# JP_Eagle_Daughter_Board.net
KiCad netlist of a schematic drawn in EAGLE
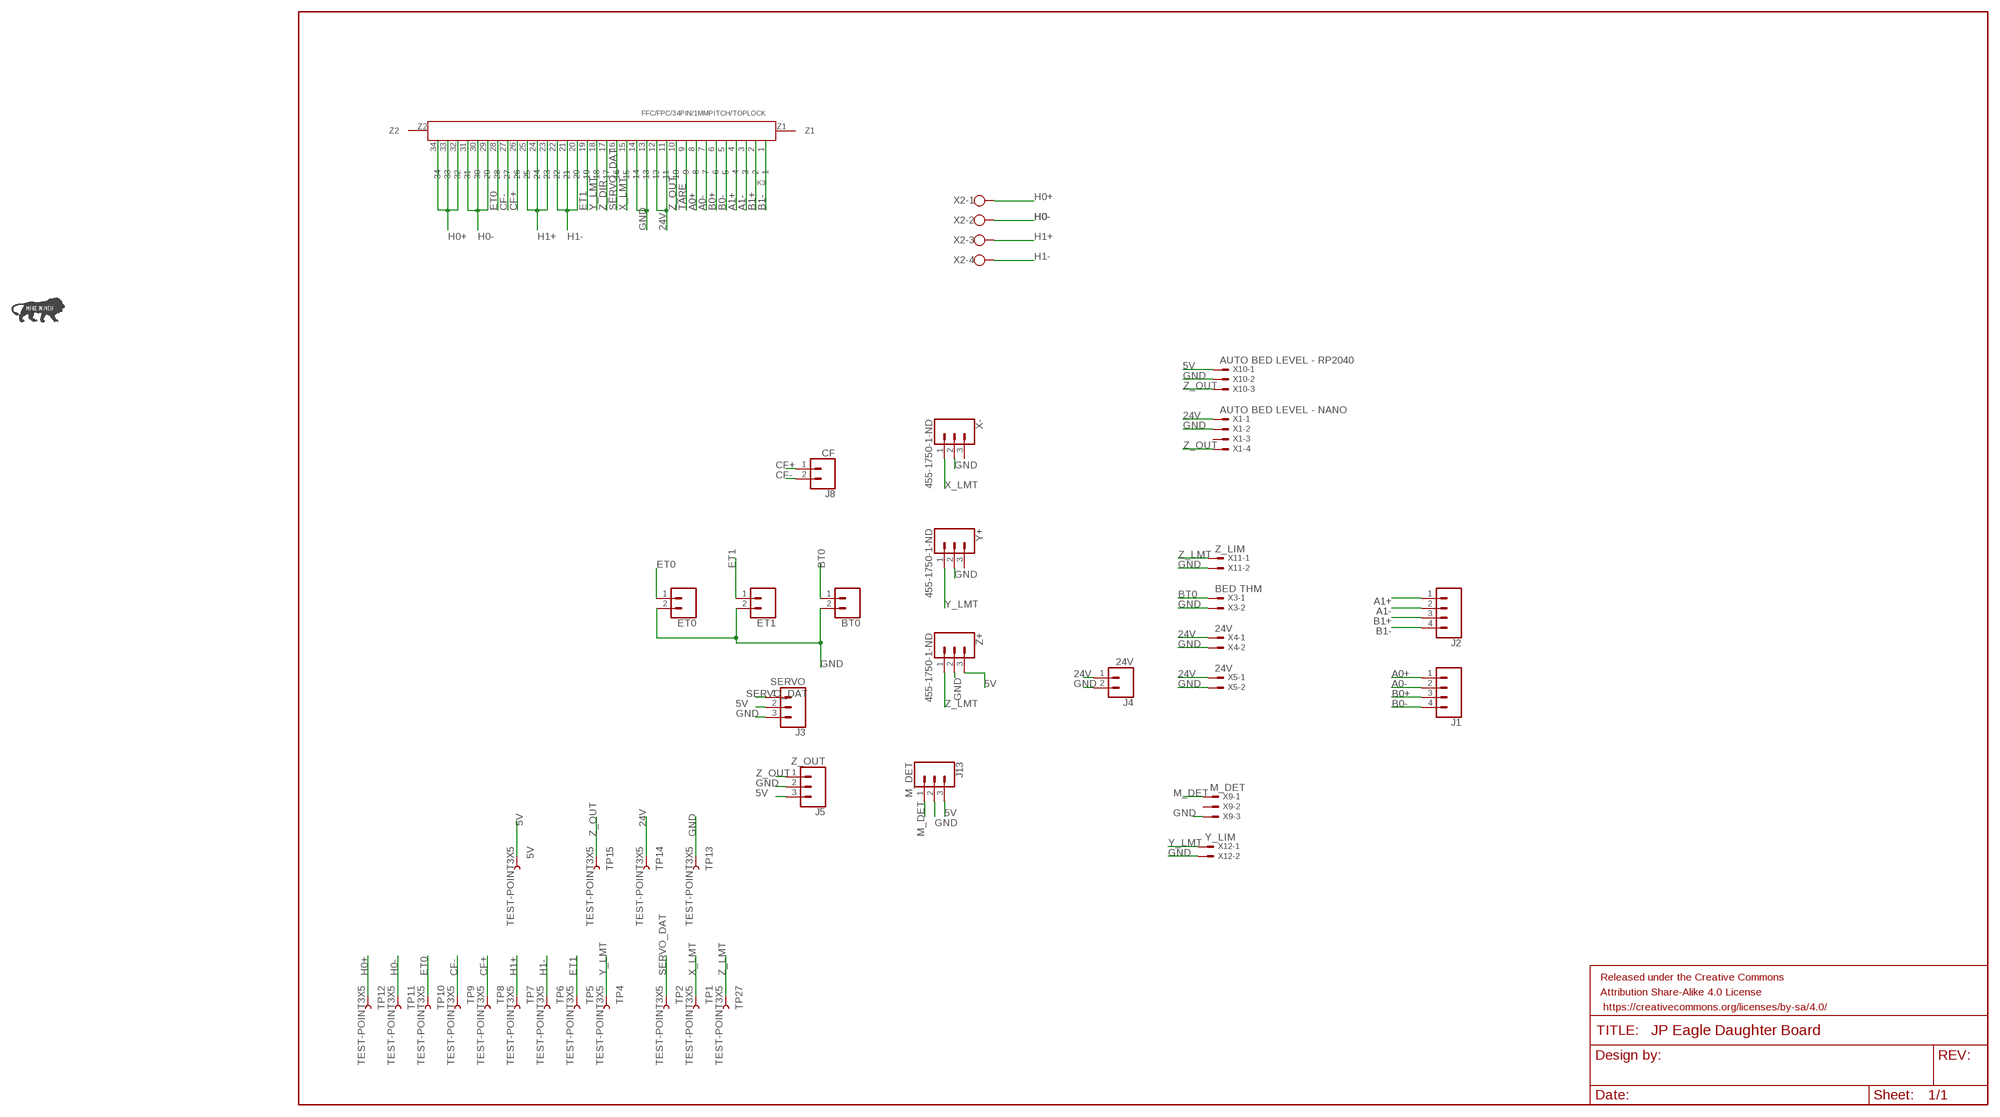
[diagram p0: schematic, sheet 1]

(export (version "E")
  (design (tool "Eeschema 10.0.6"))
  (components
    (comp (ref "5V")
      (value "TEST-POINT3X5")
      (footprint "eagle-import:PAD.03X.05")
      (libsource (lib "eagle-import") (part "TEST-POINT3X5"))
    )
    (comp (ref "BT0")
      (value "CONN_02")
      (footprint "eagle-import:1X02")
      (libsource (lib "eagle-import") (part "CONN_02"))
    )
    (comp (ref "ET0")
      (value "CONN_02")
      (footprint "eagle-import:1X02")
      (libsource (lib "eagle-import") (part "CONN_02"))
    )
    (comp (ref "ET1")
      (value "CONN_02")
      (footprint "eagle-import:1X02")
      (libsource (lib "eagle-import") (part "CONN_02"))
    )
    (comp (ref "FRAME1")
      (value "FRAME-LEDGER")
      (footprint "eagle-import:CREATIVE_COMMONS")
      (libsource (lib "eagle-import") (part "FRAME-LEDGER"))
    )
    (comp (ref "J1")
      (value "CONN_04")
      (footprint "eagle-import:1X04")
      (libsource (lib "eagle-import") (part "CONN_04"))
    )
    (comp (ref "J2")
      (value "CONN_04")
      (footprint "eagle-import:1X04")
      (libsource (lib "eagle-import") (part "CONN_04"))
    )
    (comp (ref "J3")
      (value "SERVO")
      (footprint "eagle-import:1X03")
      (libsource (lib "eagle-import") (part "CONN_03"))
    )
    (comp (ref "J4")
      (value "24V")
      (footprint "eagle-import:1X02")
      (libsource (lib "eagle-import") (part "CONN_02"))
    )
    (comp (ref "J5")
      (value "Z_OUT")
      (footprint "eagle-import:1X03")
      (libsource (lib "eagle-import") (part "CONN_03"))
    )
    (comp (ref "J8")
      (value "CF")
      (footprint "eagle-import:1X02")
      (libsource (lib "eagle-import") (part "CONN_02"))
    )
    (comp (ref "J13")
      (value "M_DET")
      (footprint "eagle-import:1X03")
      (libsource (lib "eagle-import") (part "CONN_03"))
    )
    (comp (ref "K3")
      (value "FFC/FPC/34PIN/1MMPITCH/TOPLOCK")
      (footprint "eagle-import:34PIN_1MMPITCH_FFC_FPC")
      (libsource (lib "eagle-import") (part "FFC/FPC/34PIN/1MMPITCH/TOPLOCK"))
    )
    (comp (ref "TP1")
      (value "TEST-POINT3X5")
      (footprint "eagle-import:PAD.03X.05")
      (libsource (lib "eagle-import") (part "TEST-POINT3X5"))
    )
    (comp (ref "TP2")
      (value "TEST-POINT3X5")
      (footprint "eagle-import:PAD.03X.05")
      (libsource (lib "eagle-import") (part "TEST-POINT3X5"))
    )
    (comp (ref "TP4")
      (value "TEST-POINT3X5")
      (footprint "eagle-import:PAD.03X.05")
      (libsource (lib "eagle-import") (part "TEST-POINT3X5"))
    )
    (comp (ref "TP5")
      (value "TEST-POINT3X5")
      (footprint "eagle-import:PAD.03X.05")
      (libsource (lib "eagle-import") (part "TEST-POINT3X5"))
    )
    (comp (ref "TP6")
      (value "TEST-POINT3X5")
      (footprint "eagle-import:PAD.03X.05")
      (libsource (lib "eagle-import") (part "TEST-POINT3X5"))
    )
    (comp (ref "TP7")
      (value "TEST-POINT3X5")
      (footprint "eagle-import:PAD.03X.05")
      (libsource (lib "eagle-import") (part "TEST-POINT3X5"))
    )
    (comp (ref "TP8")
      (value "TEST-POINT3X5")
      (footprint "eagle-import:PAD.03X.05")
      (libsource (lib "eagle-import") (part "TEST-POINT3X5"))
    )
    (comp (ref "TP9")
      (value "TEST-POINT3X5")
      (footprint "eagle-import:PAD.03X.05")
      (libsource (lib "eagle-import") (part "TEST-POINT3X5"))
    )
    (comp (ref "TP10")
      (value "TEST-POINT3X5")
      (footprint "eagle-import:PAD.03X.05")
      (libsource (lib "eagle-import") (part "TEST-POINT3X5"))
    )
    (comp (ref "TP11")
      (value "TEST-POINT3X5")
      (footprint "eagle-import:PAD.03X.05")
      (libsource (lib "eagle-import") (part "TEST-POINT3X5"))
    )
    (comp (ref "TP12")
      (value "TEST-POINT3X5")
      (footprint "eagle-import:PAD.03X.05")
      (libsource (lib "eagle-import") (part "TEST-POINT3X5"))
    )
    (comp (ref "TP13")
      (value "TEST-POINT3X5")
      (footprint "eagle-import:PAD.03X.05")
      (libsource (lib "eagle-import") (part "TEST-POINT3X5"))
    )
    (comp (ref "TP14")
      (value "TEST-POINT3X5")
      (footprint "eagle-import:PAD.03X.05")
      (libsource (lib "eagle-import") (part "TEST-POINT3X5"))
    )
    (comp (ref "TP15")
      (value "TEST-POINT3X5")
      (footprint "eagle-import:PAD.03X.05")
      (libsource (lib "eagle-import") (part "TEST-POINT3X5"))
    )
    (comp (ref "TP27")
      (value "TEST-POINT3X5")
      (footprint "eagle-import:PAD.03X.05")
      (libsource (lib "eagle-import") (part "TEST-POINT3X5"))
    )
    (comp (ref "U$2")
      (value "MAKEININDIA")
      (footprint "eagle-import:MAKEININDIA")
      (libsource (lib "eagle-import") (part "MAKEININDIA"))
    )
    (comp (ref "X-")
      (value "455-1750-1-ND")
      (footprint "eagle-import:1X03")
      (libsource (lib "eagle-import") (part "CONN_03"))
    )
    (comp (ref "X1")
      (value "AUTO BED LEVEL - NANO")
      (footprint "eagle-import:JST-XH-04-PACKAGE-LONG-PAD")
      (libsource (lib "eagle-import") (part "JST-XH-04-PIN-LONG-PAD"))
    )
    (comp (ref "X2")
      (value "W237-4")
      (footprint "eagle-import:W237-4")
      (libsource (lib "eagle-import") (part "W237-4"))
    )
    (comp (ref "X3")
      (value "BED THM")
      (footprint "eagle-import:JST-XH-02-PACKAGE-LONG-PAD")
      (libsource (lib "eagle-import") (part "JST-XH-02-PIN-LONG-PAD"))
    )
    (comp (ref "X4")
      (value "24V")
      (footprint "eagle-import:JST-XH-02-PACKAGE-LONG-PAD")
      (libsource (lib "eagle-import") (part "JST-XH-02-PIN-LONG-PAD"))
    )
    (comp (ref "X5")
      (value "24V")
      (footprint "eagle-import:JST-XH-02-PACKAGE-LONG-PAD")
      (libsource (lib "eagle-import") (part "JST-XH-02-PIN-LONG-PAD"))
    )
    (comp (ref "X9")
      (value "M_DET")
      (footprint "eagle-import:JST-XH-03-PACKAGE-LONG-PAD")
      (libsource (lib "eagle-import") (part "JST-XH-03-PIN-LONG-PAD"))
    )
    (comp (ref "X10")
      (value "AUTO BED LEVEL - RP2040")
      (footprint "eagle-import:JST-XH-03-PACKAGE-LONG-PAD")
      (libsource (lib "eagle-import") (part "JST-XH-03-PIN-LONG-PAD"))
    )
    (comp (ref "X11")
      (value "Z_LIM")
      (footprint "eagle-import:JST-XH-02-PACKAGE-LONG-PAD")
      (libsource (lib "eagle-import") (part "JST-XH-02-PIN-LONG-PAD"))
    )
    (comp (ref "X12")
      (value "Y_LIM")
      (footprint "eagle-import:JST-XH-02-PACKAGE-LONG-PAD")
      (libsource (lib "eagle-import") (part "JST-XH-02-PIN-LONG-PAD"))
    )
    (comp (ref "Y+")
      (value "455-1750-1-ND")
      (footprint "eagle-import:1X03")
      (libsource (lib "eagle-import") (part "CONN_03"))
    )
    (comp (ref "Z+")
      (value "455-1750-1-ND")
      (footprint "eagle-import:1X03")
      (libsource (lib "eagle-import") (part "CONN_03"))
    )
  )
  (nets
    (net (code "1") (name "/5V") (class "Default")
      (node (ref "5V") (pin "P$1") (pinfunction "1_P$1") (pintype "bidirectional"))
      (node (ref "J13") (pin "3") (pinfunction "3_3") (pintype "passive"))
      (node (ref "J3") (pin "2") (pinfunction "2_2") (pintype "passive"))
      (node (ref "J5") (pin "3") (pinfunction "3_3") (pintype "passive"))
      (node (ref "X10") (pin "1") (pinfunction "S_1") (pintype "passive"))
      (node (ref "Z+") (pin "3") (pinfunction "3_3") (pintype "passive"))
    )
    (net (code "2") (name "/24V") (class "Default")
      (node (ref "J4") (pin "1") (pinfunction "1_1") (pintype "passive"))
      (node (ref "K3") (pin "11") (pinfunction "11_11") (pintype "bidirectional"))
      (node (ref "K3") (pin "12") (pinfunction "12_12") (pintype "bidirectional"))
      (node (ref "TP14") (pin "P$1") (pinfunction "1_P$1") (pintype "bidirectional"))
      (node (ref "X1") (pin "1") (pinfunction "S_1") (pintype "passive"))
      (node (ref "X4") (pin "1") (pinfunction "S_1") (pintype "passive"))
      (node (ref "X5") (pin "1") (pinfunction "S_1") (pintype "passive"))
    )
    (net (code "3") (name "/A0+") (class "Default")
      (node (ref "J1") (pin "1") (pinfunction "1_1") (pintype "passive"))
      (node (ref "K3") (pin "8") (pinfunction "8_8") (pintype "bidirectional"))
    )
    (net (code "4") (name "/A0-") (class "Default")
      (node (ref "J1") (pin "2") (pinfunction "2_2") (pintype "passive"))
      (node (ref "K3") (pin "7") (pinfunction "7_7") (pintype "bidirectional"))
    )
    (net (code "5") (name "/A1+") (class "Default")
      (node (ref "J2") (pin "1") (pinfunction "1_1") (pintype "passive"))
      (node (ref "K3") (pin "4") (pinfunction "4_4") (pintype "bidirectional"))
    )
    (net (code "6") (name "/A1-") (class "Default")
      (node (ref "J2") (pin "2") (pinfunction "2_2") (pintype "passive"))
      (node (ref "K3") (pin "3") (pinfunction "3_3") (pintype "bidirectional"))
    )
    (net (code "7") (name "/B0+") (class "Default")
      (node (ref "J1") (pin "3") (pinfunction "3_3") (pintype "passive"))
      (node (ref "K3") (pin "6") (pinfunction "6_6") (pintype "bidirectional"))
    )
    (net (code "8") (name "/B0-") (class "Default")
      (node (ref "J1") (pin "4") (pinfunction "4_4") (pintype "passive"))
      (node (ref "K3") (pin "5") (pinfunction "5_5") (pintype "bidirectional"))
    )
    (net (code "9") (name "/B1+") (class "Default")
      (node (ref "J2") (pin "3") (pinfunction "3_3") (pintype "passive"))
      (node (ref "K3") (pin "2") (pinfunction "2_2") (pintype "bidirectional"))
    )
    (net (code "10") (name "/B1-") (class "Default")
      (node (ref "J2") (pin "4") (pinfunction "4_4") (pintype "passive"))
      (node (ref "K3") (pin "1") (pinfunction "1_1") (pintype "bidirectional"))
    )
    (net (code "11") (name "/BT0") (class "Default")
      (node (ref "BT0") (pin "1") (pinfunction "1_1") (pintype "passive"))
      (node (ref "X3") (pin "1") (pinfunction "S_1") (pintype "passive"))
    )
    (net (code "12") (name "/CF+") (class "Default")
      (node (ref "J8") (pin "1") (pinfunction "1_1") (pintype "passive"))
      (node (ref "K3") (pin "26") (pinfunction "26_26") (pintype "bidirectional"))
      (node (ref "TP8") (pin "P$1") (pinfunction "1_P$1") (pintype "bidirectional"))
    )
    (net (code "13") (name "/CF-") (class "Default")
      (node (ref "J8") (pin "2") (pinfunction "2_2") (pintype "passive"))
      (node (ref "K3") (pin "27") (pinfunction "27_27") (pintype "bidirectional"))
      (node (ref "TP9") (pin "P$1") (pinfunction "1_P$1") (pintype "bidirectional"))
    )
    (net (code "14") (name "/ET0") (class "Default")
      (node (ref "ET0") (pin "1") (pinfunction "1_1") (pintype "passive"))
      (node (ref "K3") (pin "28") (pinfunction "28_28") (pintype "bidirectional"))
      (node (ref "TP10") (pin "P$1") (pinfunction "1_P$1") (pintype "bidirectional"))
    )
    (net (code "15") (name "/ET1") (class "Default")
      (node (ref "ET1") (pin "1") (pinfunction "1_1") (pintype "passive"))
      (node (ref "K3") (pin "19") (pinfunction "19_19") (pintype "bidirectional"))
      (node (ref "TP5") (pin "P$1") (pinfunction "1_P$1") (pintype "bidirectional"))
    )
    (net (code "16") (name "/GND") (class "Default")
      (node (ref "BT0") (pin "2") (pinfunction "2_2") (pintype "passive"))
      (node (ref "ET0") (pin "2") (pinfunction "2_2") (pintype "passive"))
      (node (ref "ET1") (pin "2") (pinfunction "2_2") (pintype "passive"))
      (node (ref "J13") (pin "2") (pinfunction "2_2") (pintype "passive"))
      (node (ref "J3") (pin "3") (pinfunction "3_3") (pintype "passive"))
      (node (ref "J4") (pin "2") (pinfunction "2_2") (pintype "passive"))
      (node (ref "J5") (pin "2") (pinfunction "2_2") (pintype "passive"))
      (node (ref "K3") (pin "13") (pinfunction "13_13") (pintype "bidirectional"))
      (node (ref "K3") (pin "14") (pinfunction "14_14") (pintype "bidirectional"))
      (node (ref "TP13") (pin "P$1") (pinfunction "1_P$1") (pintype "bidirectional"))
      (node (ref "X-") (pin "2") (pinfunction "2_2") (pintype "passive"))
      (node (ref "X1") (pin "2") (pinfunction "S_2") (pintype "passive"))
      (node (ref "X10") (pin "2") (pinfunction "S_2") (pintype "passive"))
      (node (ref "X11") (pin "2") (pinfunction "S_2") (pintype "passive"))
      (node (ref "X12") (pin "2") (pinfunction "S_2") (pintype "passive"))
      (node (ref "X3") (pin "2") (pinfunction "S_2") (pintype "passive"))
      (node (ref "X4") (pin "2") (pinfunction "S_2") (pintype "passive"))
      (node (ref "X5") (pin "2") (pinfunction "S_2") (pintype "passive"))
      (node (ref "X9") (pin "3") (pinfunction "S_3") (pintype "passive"))
      (node (ref "Y+") (pin "2") (pinfunction "2_2") (pintype "passive"))
      (node (ref "Z+") (pin "2") (pinfunction "2_2") (pintype "passive"))
    )
    (net (code "17") (name "/H0+") (class "Default")
      (node (ref "K3") (pin "32") (pinfunction "32_32") (pintype "bidirectional"))
      (node (ref "K3") (pin "33") (pinfunction "33_33") (pintype "bidirectional"))
      (node (ref "K3") (pin "34") (pinfunction "34_34") (pintype "bidirectional"))
      (node (ref "TP12") (pin "P$1") (pinfunction "1_P$1") (pintype "bidirectional"))
      (node (ref "X2") (pin "1") (pinfunction "KL_1") (pintype "passive"))
    )
    (net (code "18") (name "/H0-") (class "Default")
      (node (ref "K3") (pin "29") (pinfunction "29_29") (pintype "bidirectional"))
      (node (ref "K3") (pin "30") (pinfunction "30_30") (pintype "bidirectional"))
      (node (ref "K3") (pin "31") (pinfunction "31_31") (pintype "bidirectional"))
      (node (ref "TP11") (pin "P$1") (pinfunction "1_P$1") (pintype "bidirectional"))
      (node (ref "X2") (pin "2") (pinfunction "KL_2") (pintype "passive"))
    )
    (net (code "19") (name "/H1+") (class "Default")
      (node (ref "K3") (pin "23") (pinfunction "23_23") (pintype "bidirectional"))
      (node (ref "K3") (pin "24") (pinfunction "24_24") (pintype "bidirectional"))
      (node (ref "K3") (pin "25") (pinfunction "25_25") (pintype "bidirectional"))
      (node (ref "TP7") (pin "P$1") (pinfunction "1_P$1") (pintype "bidirectional"))
      (node (ref "X2") (pin "3") (pinfunction "KL_3") (pintype "passive"))
    )
    (net (code "20") (name "/H1-") (class "Default")
      (node (ref "K3") (pin "20") (pinfunction "20_20") (pintype "bidirectional"))
      (node (ref "K3") (pin "21") (pinfunction "21_21") (pintype "bidirectional"))
      (node (ref "K3") (pin "22") (pinfunction "22_22") (pintype "bidirectional"))
      (node (ref "TP6") (pin "P$1") (pinfunction "1_P$1") (pintype "bidirectional"))
      (node (ref "X2") (pin "4") (pinfunction "KL_4") (pintype "passive"))
    )
    (net (code "21") (name "/M_DET") (class "Default")
      (node (ref "J13") (pin "1") (pinfunction "1_1") (pintype "passive"))
      (node (ref "X9") (pin "1") (pinfunction "S_1") (pintype "passive"))
    )
    (net (code "22") (name "/SERVO_DAT") (class "Default")
      (node (ref "J3") (pin "1") (pinfunction "1_1") (pintype "passive"))
      (node (ref "K3") (pin "16") (pinfunction "16_16") (pintype "bidirectional"))
      (node (ref "TP2") (pin "P$1") (pinfunction "1_P$1") (pintype "bidirectional"))
    )
    (net (code "23") (name "/TARE") (class "Default")
      (node (ref "K3") (pin "9") (pinfunction "9_9") (pintype "bidirectional"))
    )
    (net (code "24") (name "/X_LMT") (class "Default")
      (node (ref "K3") (pin "15") (pinfunction "15_15") (pintype "bidirectional"))
      (node (ref "TP1") (pin "P$1") (pinfunction "1_P$1") (pintype "bidirectional"))
      (node (ref "X-") (pin "1") (pinfunction "1_1") (pintype "passive"))
    )
    (net (code "25") (name "/Y_LMT") (class "Default")
      (node (ref "K3") (pin "18") (pinfunction "18_18") (pintype "bidirectional"))
      (node (ref "TP4") (pin "P$1") (pinfunction "1_P$1") (pintype "bidirectional"))
      (node (ref "X12") (pin "1") (pinfunction "S_1") (pintype "passive"))
      (node (ref "Y+") (pin "1") (pinfunction "1_1") (pintype "passive"))
    )
    (net (code "26") (name "/Z_DIR") (class "Default")
      (node (ref "K3") (pin "17") (pinfunction "17_17") (pintype "bidirectional"))
    )
    (net (code "27") (name "/Z_LMT") (class "Default")
      (node (ref "TP27") (pin "P$1") (pinfunction "1_P$1") (pintype "bidirectional"))
      (node (ref "X11") (pin "1") (pinfunction "S_1") (pintype "passive"))
      (node (ref "Z+") (pin "1") (pinfunction "1_1") (pintype "passive"))
    )
    (net (code "28") (name "/Z_OUT") (class "Default")
      (node (ref "J5") (pin "1") (pinfunction "1_1") (pintype "passive"))
      (node (ref "K3") (pin "10") (pinfunction "10_10") (pintype "bidirectional"))
      (node (ref "TP15") (pin "P$1") (pinfunction "1_P$1") (pintype "bidirectional"))
      (node (ref "X1") (pin "4") (pinfunction "S_4") (pintype "passive"))
      (node (ref "X10") (pin "3") (pinfunction "S_3") (pintype "passive"))
    )
    (net (code "29") (name "unconnected-(K3-PadZ1)") (class "Default")
      (node (ref "K3") (pin "Z1") (pinfunction "Z1_Z1") (pintype "bidirectional"))
    )
    (net (code "30") (name "unconnected-(K3-PadZ2)") (class "Default")
      (node (ref "K3") (pin "Z2") (pinfunction "Z2_Z2") (pintype "bidirectional"))
    )
    (net (code "31") (name "unconnected-(X--Pad3)") (class "Default")
      (node (ref "X-") (pin "3") (pinfunction "3_3") (pintype "passive"))
    )
    (net (code "32") (name "unconnected-(X1C-S-Pad3)") (class "Default")
      (node (ref "X1") (pin "3") (pinfunction "S_3") (pintype "passive"))
    )
    (net (code "33") (name "unconnected-(X9B-S-Pad2)") (class "Default")
      (node (ref "X9") (pin "2") (pinfunction "S_2") (pintype "passive"))
    )
    (net (code "34") (name "unconnected-(Y+-Pad3)") (class "Default")
      (node (ref "Y+") (pin "3") (pinfunction "3_3") (pintype "passive"))
    )
  )
)
